# CAN.net
KiCad netlist of a schematic drawn in Altium Designer
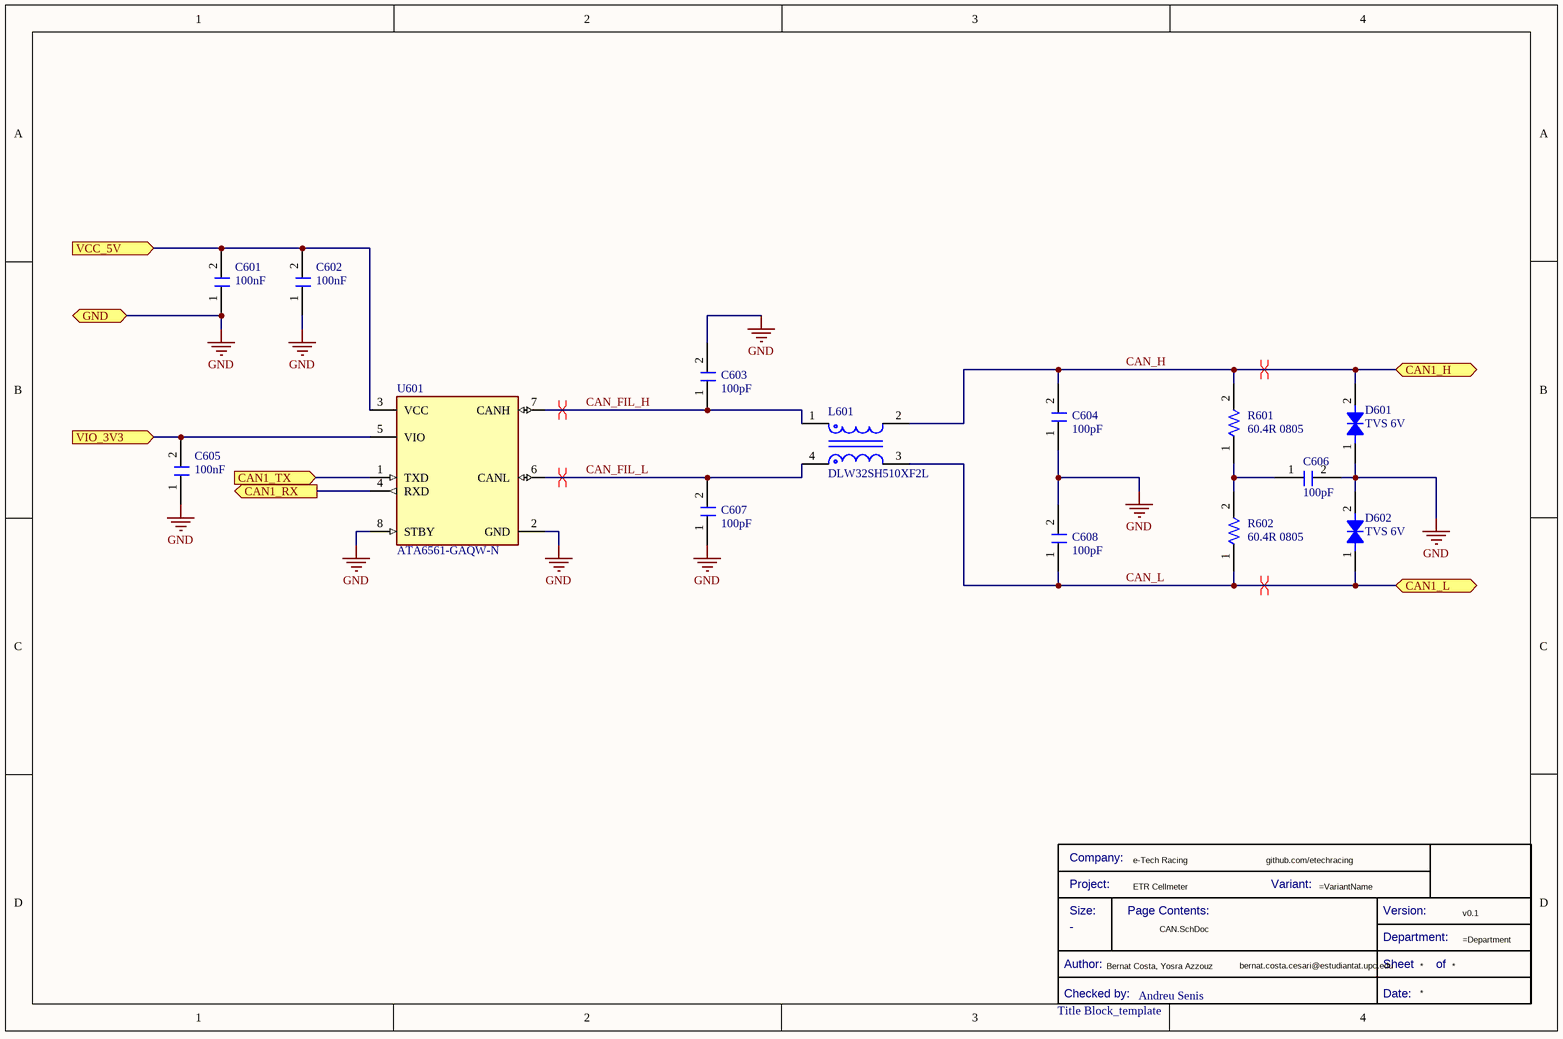
[diagram p0: CAN.SchDoc]

(export (version "E")
  (design (tool "Eeschema 10.0.6"))
  (components
    (comp (ref "C601")
      (value "100nF")
      (footprint "C0805FNPC-R")
      (description "Cap, 0.1ΜF, 50V, 10%, X7R, 0805")
      (fields
        (field (name "TOLERANCE") "10%")
        (field (name "Comment") "C100n-50V-0805FNPC-X7R")
        (field (name ".CREATOR") "DR")
      )
      (libsource (lib "EMEA- E-Tech Racing- I'Escola d'Enginyeria de Barcelona Est") (part "C100p-50V-0805FNPC-C0G/NP0"))
    )
    (comp (ref "C602")
      (value "100nF")
      (footprint "C0805FNPC-R")
      (description "Cap, 0.1ΜF, 50V, 10%, X7R, 0805")
      (fields
        (field (name "TOLERANCE") "10%")
        (field (name "Comment") "C100n-50V-0805FNPC-X7R")
        (field (name ".CREATOR") "DR")
      )
      (libsource (lib "EMEA- E-Tech Racing- I'Escola d'Enginyeria de Barcelona Est") (part "C100p-50V-0805FNPC-C0G/NP0"))
    )
    (comp (ref "C603")
      (value "100pF")
      (footprint "C0805FNPC-W")
      (fields
        (field (name "MANUFACTURER PART NUMBER") "885012007057")
        (field (name "MANUFACTURER") "Wurth Electronics")
        (field (name "TOLERANCE") "5%")
        (field (name ".CREATOR") "DR")
      )
      (libsource (lib "EMEA- E-Tech Racing- I'Escola d'Enginyeria de Barcelona Est") (part "C100p-50V-0805FNPC-C0G/NP0"))
    )
    (comp (ref "C604")
      (value "100pF")
      (footprint "C0805FNPC-W")
      (fields
        (field (name "MANUFACTURER PART NUMBER") "885012007057")
        (field (name "MANUFACTURER") "Wurth Electronics")
        (field (name "TOLERANCE") "5%")
        (field (name ".CREATOR") "DR")
      )
      (libsource (lib "EMEA- E-Tech Racing- I'Escola d'Enginyeria de Barcelona Est") (part "C100p-50V-0805FNPC-C0G/NP0"))
    )
    (comp (ref "C605")
      (value "100nF")
      (footprint "C0805FNPC-R")
      (description "Cap, 0.1ΜF, 50V, 10%, X7R, 0805")
      (fields
        (field (name "TOLERANCE") "10%")
        (field (name "Comment") "C100n-50V-0805FNPC-X7R")
        (field (name ".CREATOR") "DR")
      )
      (libsource (lib "EMEA- E-Tech Racing- I'Escola d'Enginyeria de Barcelona Est") (part "C100p-50V-0805FNPC-C0G/NP0"))
    )
    (comp (ref "C606")
      (value "100pF")
      (footprint "C0805FNPC-W")
      (fields
        (field (name "MANUFACTURER PART NUMBER") "885012007057")
        (field (name "MANUFACTURER") "Wurth Electronics")
        (field (name "TOLERANCE") "5%")
        (field (name ".CREATOR") "DR")
      )
      (libsource (lib "EMEA- E-Tech Racing- I'Escola d'Enginyeria de Barcelona Est") (part "C100p-50V-0805FNPC-C0G/NP0"))
    )
    (comp (ref "C607")
      (value "100pF")
      (footprint "C0805FNPC-W")
      (fields
        (field (name "MANUFACTURER PART NUMBER") "885012007057")
        (field (name "MANUFACTURER") "Wurth Electronics")
        (field (name "TOLERANCE") "5%")
        (field (name ".CREATOR") "DR")
      )
      (libsource (lib "EMEA- E-Tech Racing- I'Escola d'Enginyeria de Barcelona Est") (part "C100p-50V-0805FNPC-C0G/NP0"))
    )
    (comp (ref "C608")
      (value "100pF")
      (footprint "C0805FNPC-W")
      (fields
        (field (name "MANUFACTURER PART NUMBER") "885012007057")
        (field (name "MANUFACTURER") "Wurth Electronics")
        (field (name "TOLERANCE") "5%")
        (field (name ".CREATOR") "DR")
      )
      (libsource (lib "EMEA- E-Tech Racing- I'Escola d'Enginyeria de Barcelona Est") (part "C100p-50V-0805FNPC-C0G/NP0"))
    )
    (comp (ref "D601")
      (value "TVS 6V")
      (footprint "DTVS-DO-214AC")
      (description "TVS diode [Würth Elektronik] 824501600 TVS diode")
      (fields
        (field (name "MANUFACTURER") "Wurth Electronics")
        (field (name "MANUFACTURER PART NUMBER") "824501600")
        (field (name ".CREATOR") "DO")
      )
      (libsource (lib "EMEA- E-Tech Racing- I'Escola d'Enginyeria de Barcelona Est") (part "DTVS-BD-30k-SOD323"))
    )
    (comp (ref "D602")
      (value "TVS 6V")
      (footprint "DTVS-DO-214AC")
      (description "TVS diode [Würth Elektronik] 824501600 TVS diode")
      (fields
        (field (name "MANUFACTURER") "Wurth Electronics")
        (field (name "MANUFACTURER PART NUMBER") "824501600")
        (field (name ".CREATOR") "DO")
      )
      (libsource (lib "EMEA- E-Tech Racing- I'Escola d'Enginyeria de Barcelona Est") (part "DTVS-BD-30k-SOD323"))
    )
    (comp (ref "L601")
      (value "DLW32SH510XF2L")
      (footprint "FP-DLW32PH-MFG")
      (description "Cmc 51UH 200MA 2LN SMD AEC-Q200")
      (libsource (lib "EMEA- E-Tech Racing- I'Escola d'Enginyeria de Barcelona Est") (part "a6a0dbd1df74ddf8f77a2a25288fb30"))
    )
    (comp (ref "R601")
      (value "60.4R 0805")
      (footprint "R0805FTK")
      (description "Res Thin Film 0805 60.4 Ohm 0.1% 1/8W ±25ppm/°C Molded SMD SMD Punched Carrier T/R")
      (fields
        (field (name "TOLERANCE") "0.1%")
        (field (name "Comment") "R60-0805FTN")
        (field (name ".CREATOR") "DR")
      )
      (libsource (lib "EMEA- E-Tech Racing- I'Escola d'Enginyeria de Barcelona Est") (part "R9.09K-1206FTK"))
    )
    (comp (ref "R602")
      (value "60.4R 0805")
      (footprint "R0805FTK")
      (description "Res Thin Film 0805 60.4 Ohm 0.1% 1/8W ±25ppm/°C Molded SMD SMD Punched Carrier T/R")
      (fields
        (field (name "TOLERANCE") "0.1%")
        (field (name "Comment") "R60-0805FTN")
        (field (name ".CREATOR") "DR")
      )
      (libsource (lib "EMEA- E-Tech Racing- I'Escola d'Enginyeria de Barcelona Est") (part "R9.09K-1206FTK"))
    )
    (comp (ref "U601")
      (value "ATA6561-GAQW-N")
      (footprint "FP-C04-057-OA-MFG")
      (description "CAN Transceiver, 1-Trnsvr, PDSO8")
      (libsource (lib "EMEA- E-Tech Racing- I'Escola d'Enginyeria de Barcelona Est") (part "0270bb1215c60fe15aef0b32f6523a5"))
    )
  )
  (nets
    (net (code "1") (name "/CAN1_RX") (class "Default")
      (node (ref "U601") (pin "4") (pinfunction "RXD_4") (pintype "output"))
    )
    (net (code "2") (name "/CAN1_TX") (class "Default")
      (node (ref "U601") (pin "1") (pinfunction "TXD_1") (pintype "input"))
    )
    (net (code "3") (name "/CAN_FIL_H") (class "Default")
      (node (ref "C603") (pin "1") (pinfunction "1_1") (pintype "passive"))
      (node (ref "L601") (pin "1") (pinfunction "1_1") (pintype "passive"))
      (node (ref "U601") (pin "7") (pinfunction "CANH_7") (pintype "bidirectional"))
    )
    (net (code "4") (name "/CAN_FIL_L") (class "Default")
      (node (ref "C607") (pin "2") (pinfunction "2_2") (pintype "passive"))
      (node (ref "L601") (pin "4") (pinfunction "4_4") (pintype "passive"))
      (node (ref "U601") (pin "6") (pinfunction "CANL_6") (pintype "bidirectional"))
    )
    (net (code "5") (name "/CAN_H") (class "Default")
      (node (ref "C604") (pin "2") (pinfunction "2_2") (pintype "passive"))
      (node (ref "D601") (pin "2") (pinfunction "2_2") (pintype "passive"))
      (node (ref "L601") (pin "2") (pinfunction "2_2") (pintype "passive"))
      (node (ref "R601") (pin "2") (pinfunction "2_2") (pintype "passive"))
    )
    (net (code "6") (name "/CAN_L") (class "Default")
      (node (ref "C608") (pin "1") (pinfunction "1_1") (pintype "passive"))
      (node (ref "D602") (pin "1") (pinfunction "1_1") (pintype "passive"))
      (node (ref "L601") (pin "3") (pinfunction "3_3") (pintype "passive"))
      (node (ref "R602") (pin "1") (pinfunction "1_1") (pintype "passive"))
    )
    (net (code "7") (name "/VCC_5V") (class "Default")
      (node (ref "C601") (pin "2") (pinfunction "2_2") (pintype "passive"))
      (node (ref "C602") (pin "2") (pinfunction "2_2") (pintype "passive"))
      (node (ref "U601") (pin "3") (pinfunction "VCC_3") (pintype "power_in"))
    )
    (net (code "8") (name "/VIO_3V3") (class "Default")
      (node (ref "C605") (pin "2") (pinfunction "2_2") (pintype "passive"))
      (node (ref "U601") (pin "5") (pinfunction "VIO_5") (pintype "power_in"))
    )
    (net (code "9") (name "GND") (class "Default")
      (node (ref "C601") (pin "1") (pinfunction "1_1") (pintype "passive"))
      (node (ref "C602") (pin "1") (pinfunction "1_1") (pintype "passive"))
      (node (ref "C603") (pin "2") (pinfunction "2_2") (pintype "passive"))
      (node (ref "C604") (pin "1") (pinfunction "1_1") (pintype "passive"))
      (node (ref "C605") (pin "1") (pinfunction "1_1") (pintype "passive"))
      (node (ref "C606") (pin "2") (pinfunction "2_2") (pintype "passive"))
      (node (ref "C607") (pin "1") (pinfunction "1_1") (pintype "passive"))
      (node (ref "C608") (pin "2") (pinfunction "2_2") (pintype "passive"))
      (node (ref "D601") (pin "1") (pinfunction "1_1") (pintype "passive"))
      (node (ref "D602") (pin "2") (pinfunction "2_2") (pintype "passive"))
      (node (ref "U601") (pin "2") (pinfunction "GND_2") (pintype "power_in"))
      (node (ref "U601") (pin "8") (pinfunction "STBY_8") (pintype "input"))
    )
    (net (code "10") (name "Net-(C606-Pad1)") (class "Default")
      (node (ref "C606") (pin "1") (pinfunction "1_1") (pintype "passive"))
      (node (ref "R601") (pin "1") (pinfunction "1_1") (pintype "passive"))
      (node (ref "R602") (pin "2") (pinfunction "2_2") (pintype "passive"))
    )
  )
)
